# AUDIO.net
KiCad netlist of a schematic drawn in Altium Designer
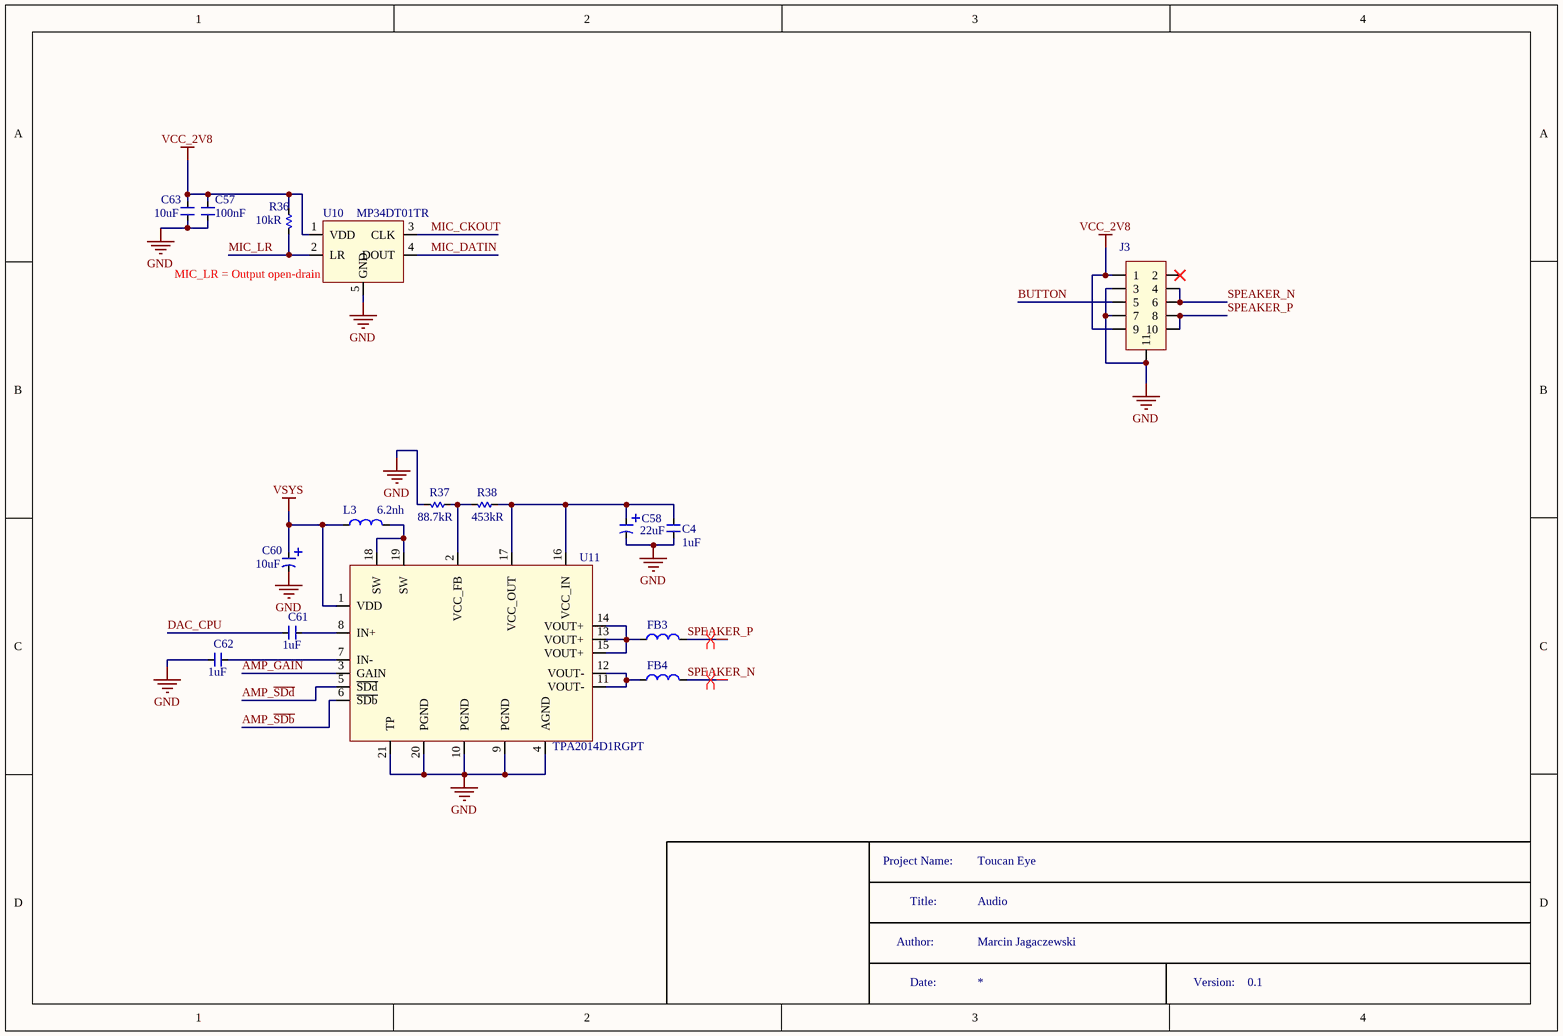
[diagram p0: AUDIO.SchDoc]

(export (version "E")
  (design (tool "Eeschema 10.0.6"))
  (components
    (comp (ref "C4")
      (value "C0402_1uF_TMK105BJ105MV-F")
      (footprint "C_0402")
      (description "CAP CER 1UF 25V X5R 0402")
      (fields
        (field (name "MANUFACTURER") "Taiyo Yuden")
        (field (name "MANUFACTURER PART NUMBER") "TMK105BJ105MV-F")
        (field (name "CAPACITANCE") "1uF")
      )
      (libsource (lib "CAP") (part "C0402_1uF_TMK105BJ105MV-F"))
    )
    (comp (ref "C57")
      (value "C0201_100n_GRM033R6YA104KE14D")
      (footprint "C_0201")
      (description "Multilayer Ceramic Capacitors MLCC - SMD/SMT 0201 0.10uF 35volts *Derate Voltage/Temp")
      (fields
        (field (name "MANUFACTURER") "Murata")
        (field (name "MANUFACTURER PART NUMBER") "GRM033R6YA104KE14D")
        (field (name "CAPACITANCE") "100nF")
      )
      (libsource (lib "CAP") (part "C0201_100n_GRM033R6YA104KE14D"))
    )
    (comp (ref "C58")
      (value "C_22u_TANTAL_A_T491A226K006AT")
      (footprint "C_3216")
      (description "Cap Tant Solid 22uF 6.3V A CASE 10% (3.2 X 1.6 X 1.6mm) SMD 3216-18 4 Ohm 125C T/R")
      (fields
        (field (name "MANUFACTURER") "KEMET")
        (field (name "MANUFACTURER PART NUMBER") "T491A226K006AT")
        (field (name "CAPACITANCE") "22uF")
      )
      (libsource (lib "CAP") (part "C_22u_TANTAL_A_T491A226K006AT"))
    )
    (comp (ref "C60")
      (value "C_10u_TANTAL_A_T491A106K010AT7280")
      (footprint "C_3216")
      (description "CAP TANT 10UF 10V 10% 1206")
      (fields
        (field (name "MANUFACTURER") "KEMET")
        (field (name "MANUFACTURER PART NUMBER") "T491A106K010AT7280")
        (field (name "CAPACITANCE") "10uF")
      )
      (libsource (lib "CAP") (part "C_10u_TANTAL_A_T491A106K010AT7280"))
    )
    (comp (ref "C61")
      (value "C0402_1uF_TMK105BJ105MV-F")
      (footprint "C_0402")
      (description "CAP CER 1UF 25V X5R 0402")
      (fields
        (field (name "MANUFACTURER") "Taiyo Yuden")
        (field (name "MANUFACTURER PART NUMBER") "TMK105BJ105MV-F")
        (field (name "CAPACITANCE") "1uF")
      )
      (libsource (lib "CAP") (part "C0402_1uF_TMK105BJ105MV-F"))
    )
    (comp (ref "C62")
      (value "C0402_1uF_TMK105BJ105MV-F")
      (footprint "C_0402")
      (description "CAP CER 1UF 25V X5R 0402")
      (fields
        (field (name "MANUFACTURER") "Taiyo Yuden")
        (field (name "MANUFACTURER PART NUMBER") "TMK105BJ105MV-F")
        (field (name "CAPACITANCE") "1uF")
      )
      (libsource (lib "CAP") (part "C0402_1uF_TMK105BJ105MV-F"))
    )
    (comp (ref "C63")
      (value "C0402_10u_GRM155C80J106ME11D")
      (footprint "C_0402")
      (description "10µF 6.3V Ceramic Capacitor X6S 0402 (1005 Metric) 0.039\" L x 0.020\" W (1.00mm x 0.50mm)")
      (fields
        (field (name "MANUFACTURER") "Murata")
        (field (name "MANUFACTURER PART NUMBER") "GRM155C80J106ME11D")
        (field (name "CAPACITANCE") "10uF")
      )
      (libsource (lib "CAP") (part "C0402_10u_GRM155C80J106ME11D"))
    )
    (comp (ref "FB3")
      (value "BLM18EG121SN1D")
      (footprint "L_0603")
      (description "MURATA         BLM18EG121SN1D            FERRITE BEAD, 0.04OHM, 2A, 0603")
      (fields (field (name "MANUFACTURER") "Murata") (field (name "TOLERANCE") "25%"))
      (libsource (lib "IND") (part "BLM18EG121SN1D"))
    )
    (comp (ref "FB4")
      (value "BLM18EG121SN1D")
      (footprint "L_0603")
      (description "MURATA         BLM18EG121SN1D            FERRITE BEAD, 0.04OHM, 2A, 0603")
      (fields (field (name "MANUFACTURER") "Murata") (field (name "TOLERANCE") "25%"))
      (libsource (lib "IND") (part "BLM18EG121SN1D"))
    )
    (comp (ref "J3")
      (value "BM10NB(0.6)-10DS-0.4V(51)")
      (footprint "BM10NB(0.6)-10DS-0.4V(51)")
      (description "CONN RCPT 10POS 0.4MM SMD GOLD")
      (fields (field (name "MANUFACTURER") "Hirose"))
      (libsource (lib "CONN") (part "BM10NB(0.6)-10DS-0.4V(51)"))
    )
    (comp (ref "L3")
      (value "744765062A")
      (footprint "L_0402")
      (description "FIXED IND 6.2NH 760MA 83 MOHM")
      (fields
        (field (name "MANUFACTURER") "Wurth Electronics")
        (field (name "TOLERANCE") "5%")
        (field (name "INDUCTANCE") "6.2nh")
      )
      (libsource (lib "IND") (part "744765062A"))
    )
    (comp (ref "R36")
      (value "R0201_10k_ERJ-1GNF1002C")
      (footprint "R_0201")
      (description "RESISTOR, 0201, 0.05W, 1%, 10K")
      (fields
        (field (name "MANUFACTURER") "Panasonic ECG")
        (field (name "MANUFACTURER PART NUMBER") "ERJ-1GNF1002C")
        (field (name "RESISTANCE") "10kR")
      )
      (libsource (lib "RES") (part "R0201_10k_ERJ-1GNF1002C"))
    )
    (comp (ref "R37")
      (value "R0201_88.7k_ERJ-1GNF8872C")
      (footprint "R_0201")
      (description "Thick Film Resistors - SMD 0201 88.7Kohm 1% Halogen Free")
      (fields
        (field (name "MANUFACTURER") "Panasonic ECG")
        (field (name "MANUFACTURER PART NUMBER") "ERJ-1GNF8872C")
        (field (name "RESISTANCE") "88.7kR")
      )
      (libsource (lib "RES") (part "R0201_88.7k_ERJ-1GNF8872C"))
    )
    (comp (ref "R38")
      (value "R0201_453k_RC0201FR-07453KL")
      (footprint "R_0201")
      (description "Res Thick Film 0201 453K Ohm 1% 0.05W(1/20W) ±200ppm/C Molded SMD Paper T/R")
      (fields
        (field (name "MANUFACTURER") "Yageo")
        (field (name "MANUFACTURER PART NUMBER") "RC0201FR-07453KL")
        (field (name "RESISTANCE") "453kR")
      )
      (libsource (lib "RES") (part "R0201_453k_RC0201FR-07453KL"))
    )
    (comp (ref "U10")
      (value "MP34DT01TR")
      (footprint "HCLGA")
      (description "MIC MEMS DIGITAL PDM OMNI -26DB")
      (fields (field (name "MANUFACTURER") "STMicroelectronics"))
      (libsource (lib "CHIP") (part "MP34DT01TR"))
    )
    (comp (ref "U11")
      (value "TPA2014D1RGPT")
      (footprint "QFN_16x0,5")
      (description "IC AMP AUDIO PWR 1.5W D 20QFN")
      (fields
        (field (name "MANUFACTURER") "Texas Instruments")
        (field (name "MANUFACTURER PART NUMBER") "TPA2014D1RGPT")
      )
      (libsource (lib "CHIP") (part "TPA2014D1RGPT"))
    )
  )
  (nets
    (net (code "1") (name "/AMP_GAIN") (class "Default")
      (node (ref "U11") (pin "3") (pinfunction "GAIN_3") (pintype "power_in"))
    )
    (net (code "2") (name "/AMP_~{SDb}") (class "Default")
      (node (ref "U11") (pin "6") (pinfunction "~{SDb}_6") (pintype "power_in"))
    )
    (net (code "3") (name "/AMP_~{SDd}") (class "Default")
      (node (ref "U11") (pin "5") (pinfunction "~{SDd}_5") (pintype "power_in"))
    )
    (net (code "4") (name "/BUTTON") (class "Default")
      (node (ref "J3") (pin "5") (pinfunction "5_5") (pintype "passive"))
    )
    (net (code "5") (name "/DAC_CPU") (class "Default")
      (node (ref "C61") (pin "1") (pinfunction "1_1") (pintype "passive"))
    )
    (net (code "6") (name "/MIC_CKOUT") (class "Default")
      (node (ref "U10") (pin "3") (pinfunction "CLK_3") (pintype "power_in"))
    )
    (net (code "7") (name "/MIC_DATIN") (class "Default")
      (node (ref "U10") (pin "4") (pinfunction "DOUT_4") (pintype "power_in"))
    )
    (net (code "8") (name "/MIC_LR") (class "Default")
      (node (ref "R36") (pin "1") (pinfunction "1_1") (pintype "power_in"))
      (node (ref "U10") (pin "2") (pinfunction "LR_2") (pintype "power_in"))
    )
    (net (code "9") (name "/SPEAKER_N") (class "Default")
      (node (ref "FB4") (pin "2") (pinfunction "Vcc_2") (pintype "passive"))
      (node (ref "J3") (pin "4") (pinfunction "4_4") (pintype "passive"))
      (node (ref "J3") (pin "6") (pinfunction "6_6") (pintype "passive"))
    )
    (net (code "10") (name "/SPEAKER_P") (class "Default")
      (node (ref "FB3") (pin "2") (pinfunction "Vcc_2") (pintype "passive"))
      (node (ref "J3") (pin "10") (pinfunction "10_10") (pintype "passive"))
      (node (ref "J3") (pin "8") (pinfunction "8_8") (pintype "passive"))
    )
    (net (code "11") (name "GND") (class "Default")
      (node (ref "C4") (pin "1") (pinfunction "1_1") (pintype "passive"))
      (node (ref "C57") (pin "1") (pinfunction "1_1") (pintype "passive"))
      (node (ref "C58") (pin "2") (pinfunction "2_2") (pintype "passive"))
      (node (ref "C60") (pin "2") (pinfunction "2_2") (pintype "passive"))
      (node (ref "C62") (pin "1") (pinfunction "1_1") (pintype "passive"))
      (node (ref "C63") (pin "1") (pinfunction "1_1") (pintype "passive"))
      (node (ref "J3") (pin "11") (pinfunction "11_11") (pintype "passive"))
      (node (ref "J3") (pin "3") (pinfunction "3_3") (pintype "passive"))
      (node (ref "J3") (pin "7") (pinfunction "7_7") (pintype "passive"))
      (node (ref "R37") (pin "1") (pinfunction "1_1") (pintype "power_in"))
      (node (ref "U10") (pin "5") (pinfunction "GND_5") (pintype "power_in"))
      (node (ref "U11") (pin "10") (pinfunction "PGND_10") (pintype "power_in"))
      (node (ref "U11") (pin "20") (pinfunction "PGND_20") (pintype "power_in"))
      (node (ref "U11") (pin "21") (pinfunction "TP_21") (pintype "power_in"))
      (node (ref "U11") (pin "4") (pinfunction "AGND_4") (pintype "power_in"))
      (node (ref "U11") (pin "9") (pinfunction "PGND_9") (pintype "power_in"))
    )
    (net (code "12") (name "Net-(FB3-Vcc-Pad1)") (class "Default")
      (node (ref "FB3") (pin "1") (pinfunction "Vcc_1") (pintype "passive"))
      (node (ref "U11") (pin "13") (pinfunction "VOUT+_13") (pintype "power_in"))
      (node (ref "U11") (pin "14") (pinfunction "VOUT+_14") (pintype "power_in"))
      (node (ref "U11") (pin "15") (pinfunction "VOUT+_15") (pintype "power_in"))
    )
    (net (code "13") (name "Net-(FB4-Vcc-Pad1)") (class "Default")
      (node (ref "FB4") (pin "1") (pinfunction "Vcc_1") (pintype "passive"))
      (node (ref "U11") (pin "11") (pinfunction "VOUT-_11") (pintype "power_in"))
      (node (ref "U11") (pin "12") (pinfunction "VOUT-_12") (pintype "power_in"))
    )
    (net (code "14") (name "Net-(L3-Vcc-Pad2)") (class "Default")
      (node (ref "L3") (pin "2") (pinfunction "Vcc_2") (pintype "passive"))
      (node (ref "U11") (pin "18") (pinfunction "SW_18") (pintype "power_in"))
      (node (ref "U11") (pin "19") (pinfunction "SW_19") (pintype "power_in"))
    )
    (net (code "15") (name "Net-(U11-IN+)") (class "Default")
      (node (ref "C61") (pin "2") (pinfunction "2_2") (pintype "passive"))
      (node (ref "U11") (pin "8") (pinfunction "IN+_8") (pintype "power_in"))
    )
    (net (code "16") (name "Net-(U11-IN-)") (class "Default")
      (node (ref "C62") (pin "2") (pinfunction "2_2") (pintype "passive"))
      (node (ref "U11") (pin "7") (pinfunction "IN-_7") (pintype "power_in"))
    )
    (net (code "17") (name "Net-(U11-VCC_FB)") (class "Default")
      (node (ref "R37") (pin "2") (pinfunction "2_2") (pintype "power_in"))
      (node (ref "R38") (pin "1") (pinfunction "1_1") (pintype "power_in"))
      (node (ref "U11") (pin "2") (pinfunction "VCC_FB_2") (pintype "power_in"))
    )
    (net (code "18") (name "Net-(U11-VCC_IN)") (class "Default")
      (node (ref "C4") (pin "2") (pinfunction "2_2") (pintype "passive"))
      (node (ref "C58") (pin "1") (pinfunction "1_1") (pintype "passive"))
      (node (ref "R38") (pin "2") (pinfunction "2_2") (pintype "power_in"))
      (node (ref "U11") (pin "16") (pinfunction "VCC_IN_16") (pintype "power_in"))
      (node (ref "U11") (pin "17") (pinfunction "VCC_OUT_17") (pintype "power_in"))
    )
    (net (code "19") (name "VCC_2V8") (class "Default")
      (node (ref "C57") (pin "2") (pinfunction "2_2") (pintype "passive"))
      (node (ref "C63") (pin "2") (pinfunction "2_2") (pintype "passive"))
      (node (ref "J3") (pin "1") (pinfunction "1_1") (pintype "passive"))
      (node (ref "J3") (pin "9") (pinfunction "9_9") (pintype "passive"))
      (node (ref "R36") (pin "2") (pinfunction "2_2") (pintype "power_in"))
      (node (ref "U10") (pin "1") (pinfunction "VDD_1") (pintype "power_in"))
    )
    (net (code "20") (name "VSYS") (class "Default")
      (node (ref "C60") (pin "1") (pinfunction "1_1") (pintype "passive"))
      (node (ref "L3") (pin "1") (pinfunction "Vcc_1") (pintype "passive"))
      (node (ref "U11") (pin "1") (pinfunction "VDD_1") (pintype "power_in"))
    )
    (net (code "21") (name "unconnected-(J3-Pad2)") (class "Default")
      (node (ref "J3") (pin "2") (pinfunction "2_2") (pintype "passive+no_connect"))
    )
  )
)
